# sunjar-v1_1.net
KiCad netlist of a schematic drawn in EAGLE
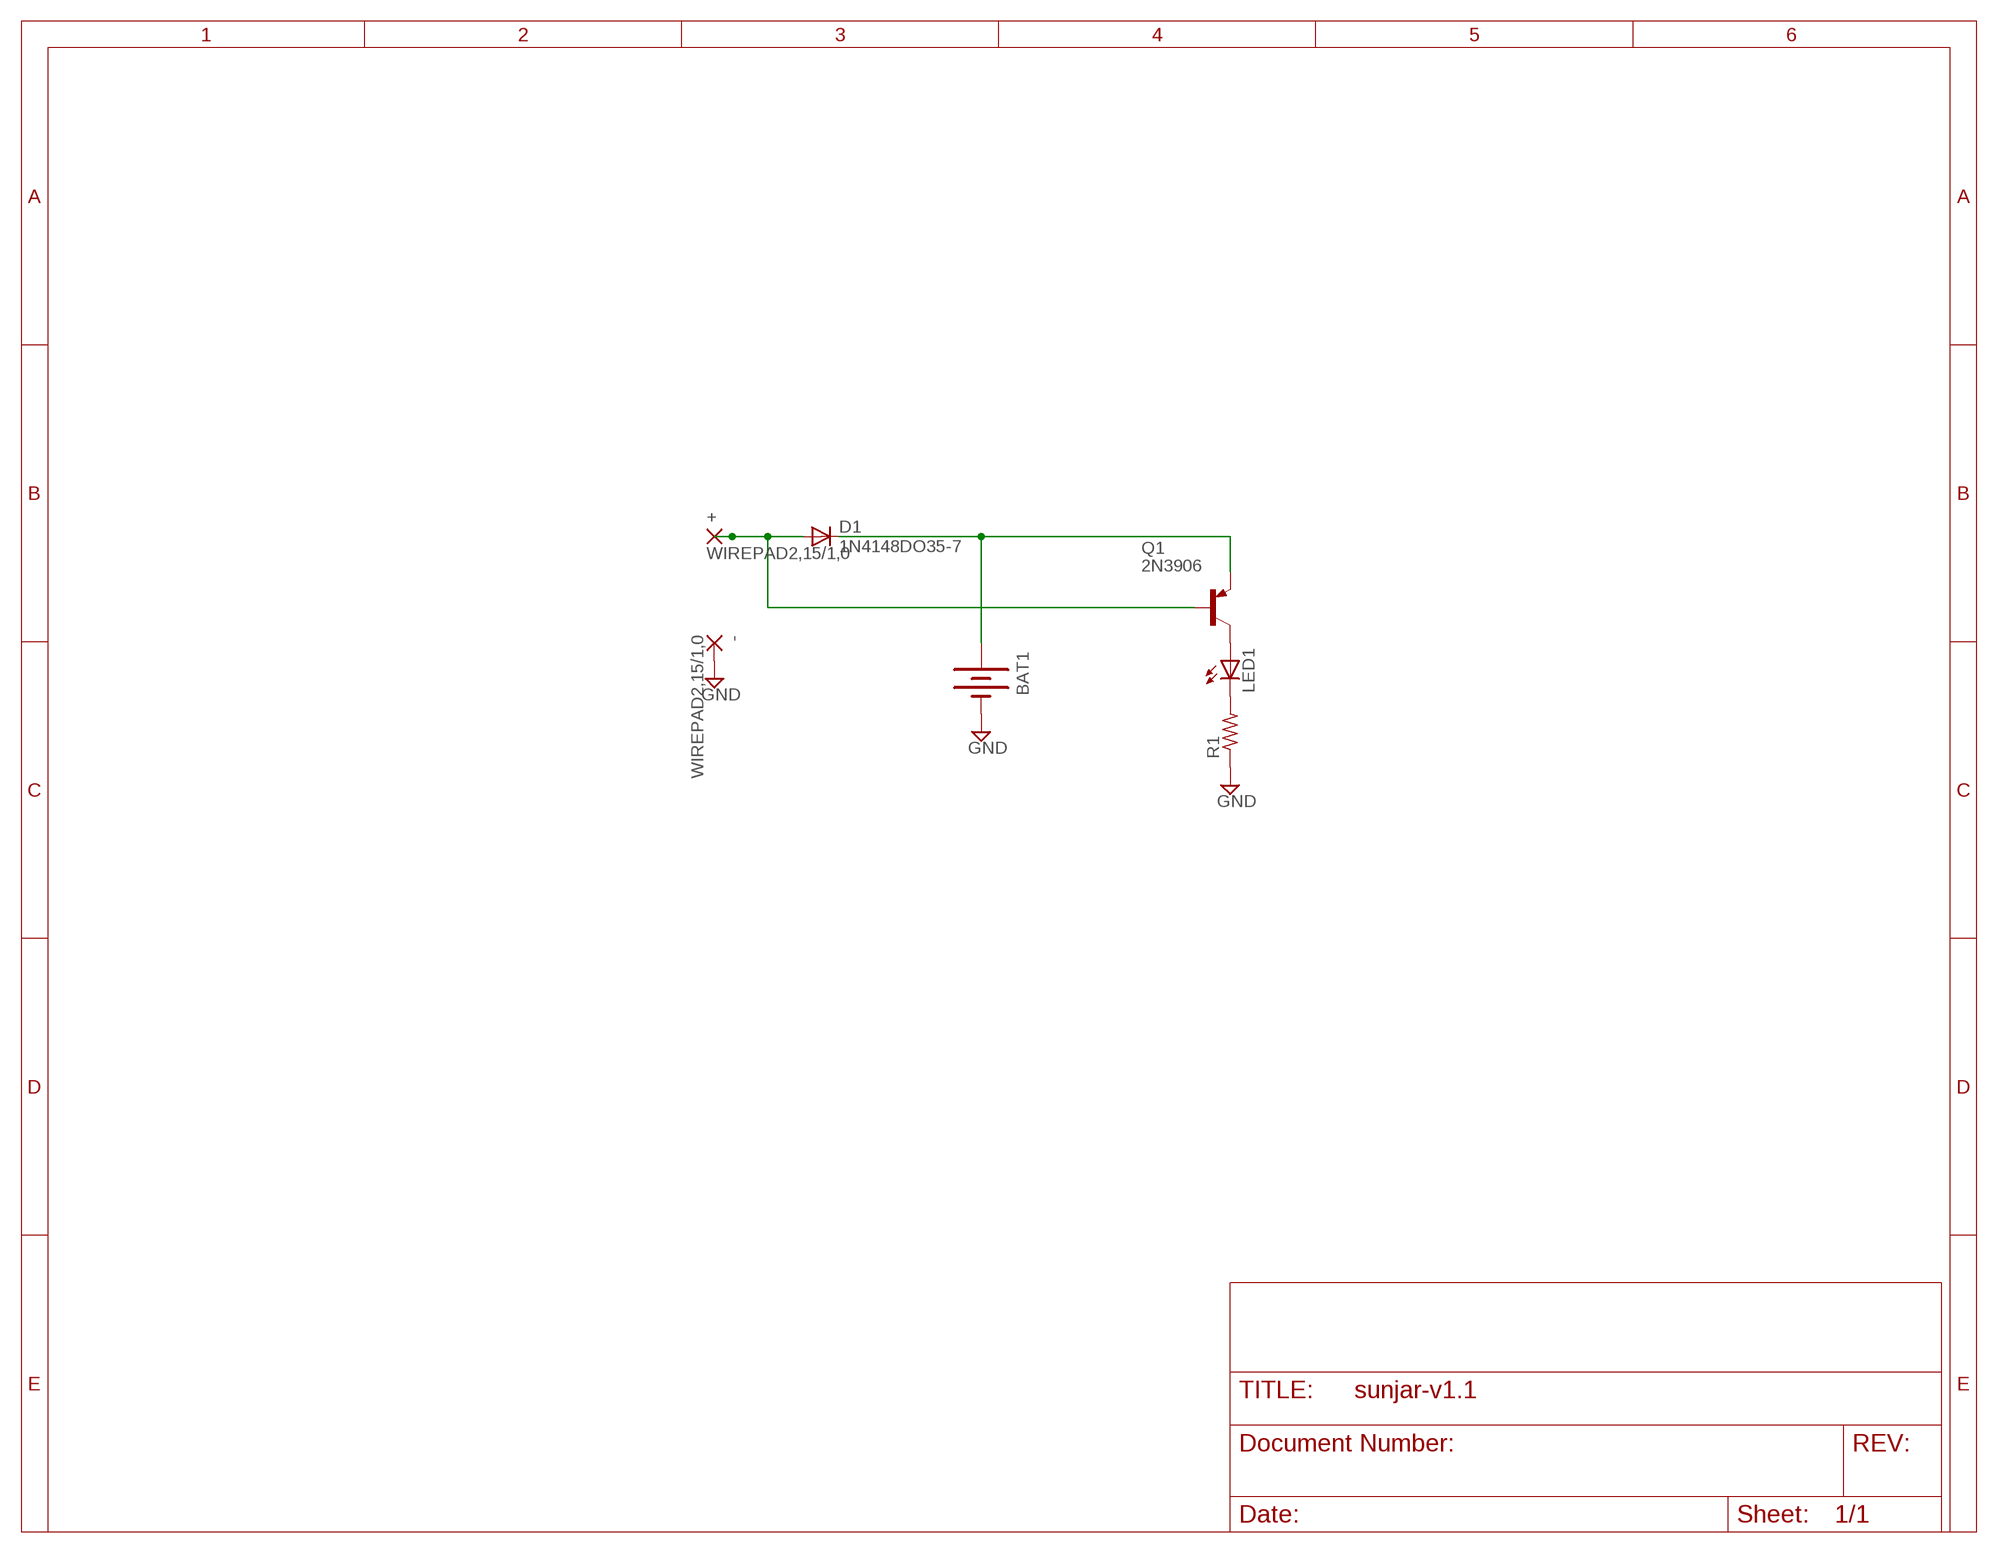
[diagram p0: schematic, sheet 1]

(export (version "E")
  (design (tool "Eeschema 10.0.6"))
  (components
    (comp (ref "+")
      (value "WIREPAD2,15/1,0")
      (footprint "eagle-import:2,15_1,0")
      (libsource (lib "eagle-import") (part "WIREPAD2,15/1,0"))
    )
    (comp (ref "-")
      (value "WIREPAD2,15/1,0")
      (footprint "eagle-import:2,15_1,0")
      (libsource (lib "eagle-import") (part "WIREPAD2,15/1,0"))
    )
    (comp (ref "BAT1")
      (value "BATTERY245PTH")
      (footprint "eagle-import:BATTCON_245MM_PTH")
      (libsource (lib "eagle-import") (part "BATTERY245PTH"))
    )
    (comp (ref "D1")
      (value "1N4148DO35-7")
      (footprint "eagle-import:DO35-7")
      (libsource (lib "eagle-import") (part "1N4148DO35-7"))
    )
    (comp (ref "LED1")
      (value "LED5MM")
      (footprint "eagle-import:LED5MM")
      (libsource (lib "eagle-import") (part "LED5MM"))
    )
    (comp (ref "Q1")
      (value "2N3906")
      (footprint "eagle-import:TO92")
      (libsource (lib "eagle-import") (part "2N3906"))
    )
    (comp (ref "R1")
      (value "R-US_0207/10")
      (footprint "eagle-import:0207_10")
      (libsource (lib "eagle-import") (part "R-US_0207/10"))
    )
  )
  (nets
    (net (code "1") (name "GND") (class "Default")
      (node (ref "-") (pin "1") (pinfunction "P_1") (pintype "passive"))
      (node (ref "BAT1") (pin "2") (pinfunction "-_2") (pintype "power_in"))
      (node (ref "R1") (pin "1") (pinfunction "1_1") (pintype "passive"))
    )
    (net (code "2") (name "Net-(+-P)") (class "Default")
      (node (ref "+") (pin "1") (pinfunction "P_1") (pintype "passive"))
      (node (ref "D1") (pin "A") (pinfunction "A_A") (pintype "passive"))
      (node (ref "Q1") (pin "2") (pinfunction "B_2") (pintype "passive"))
    )
    (net (code "3") (name "Net-(BAT1-+)") (class "Default")
      (node (ref "BAT1") (pin "3") (pinfunction "+_3") (pintype "power_in"))
      (node (ref "D1") (pin "C") (pinfunction "C_C") (pintype "passive"))
      (node (ref "Q1") (pin "3") (pinfunction "E_3") (pintype "passive"))
    )
    (net (code "4") (name "Net-(LED1-C)") (class "Default")
      (node (ref "LED1") (pin "K") (pinfunction "C_K") (pintype "passive"))
      (node (ref "R1") (pin "2") (pinfunction "2_2") (pintype "passive"))
    )
    (net (code "5") (name "Net-(Q1-C)") (class "Default")
      (node (ref "LED1") (pin "A") (pinfunction "A_A") (pintype "passive"))
      (node (ref "Q1") (pin "1") (pinfunction "C_1") (pintype "passive"))
    )
  )
)
